# STM32_MPU_IOs.net
KiCad netlist of a schematic drawn in Altium Designer
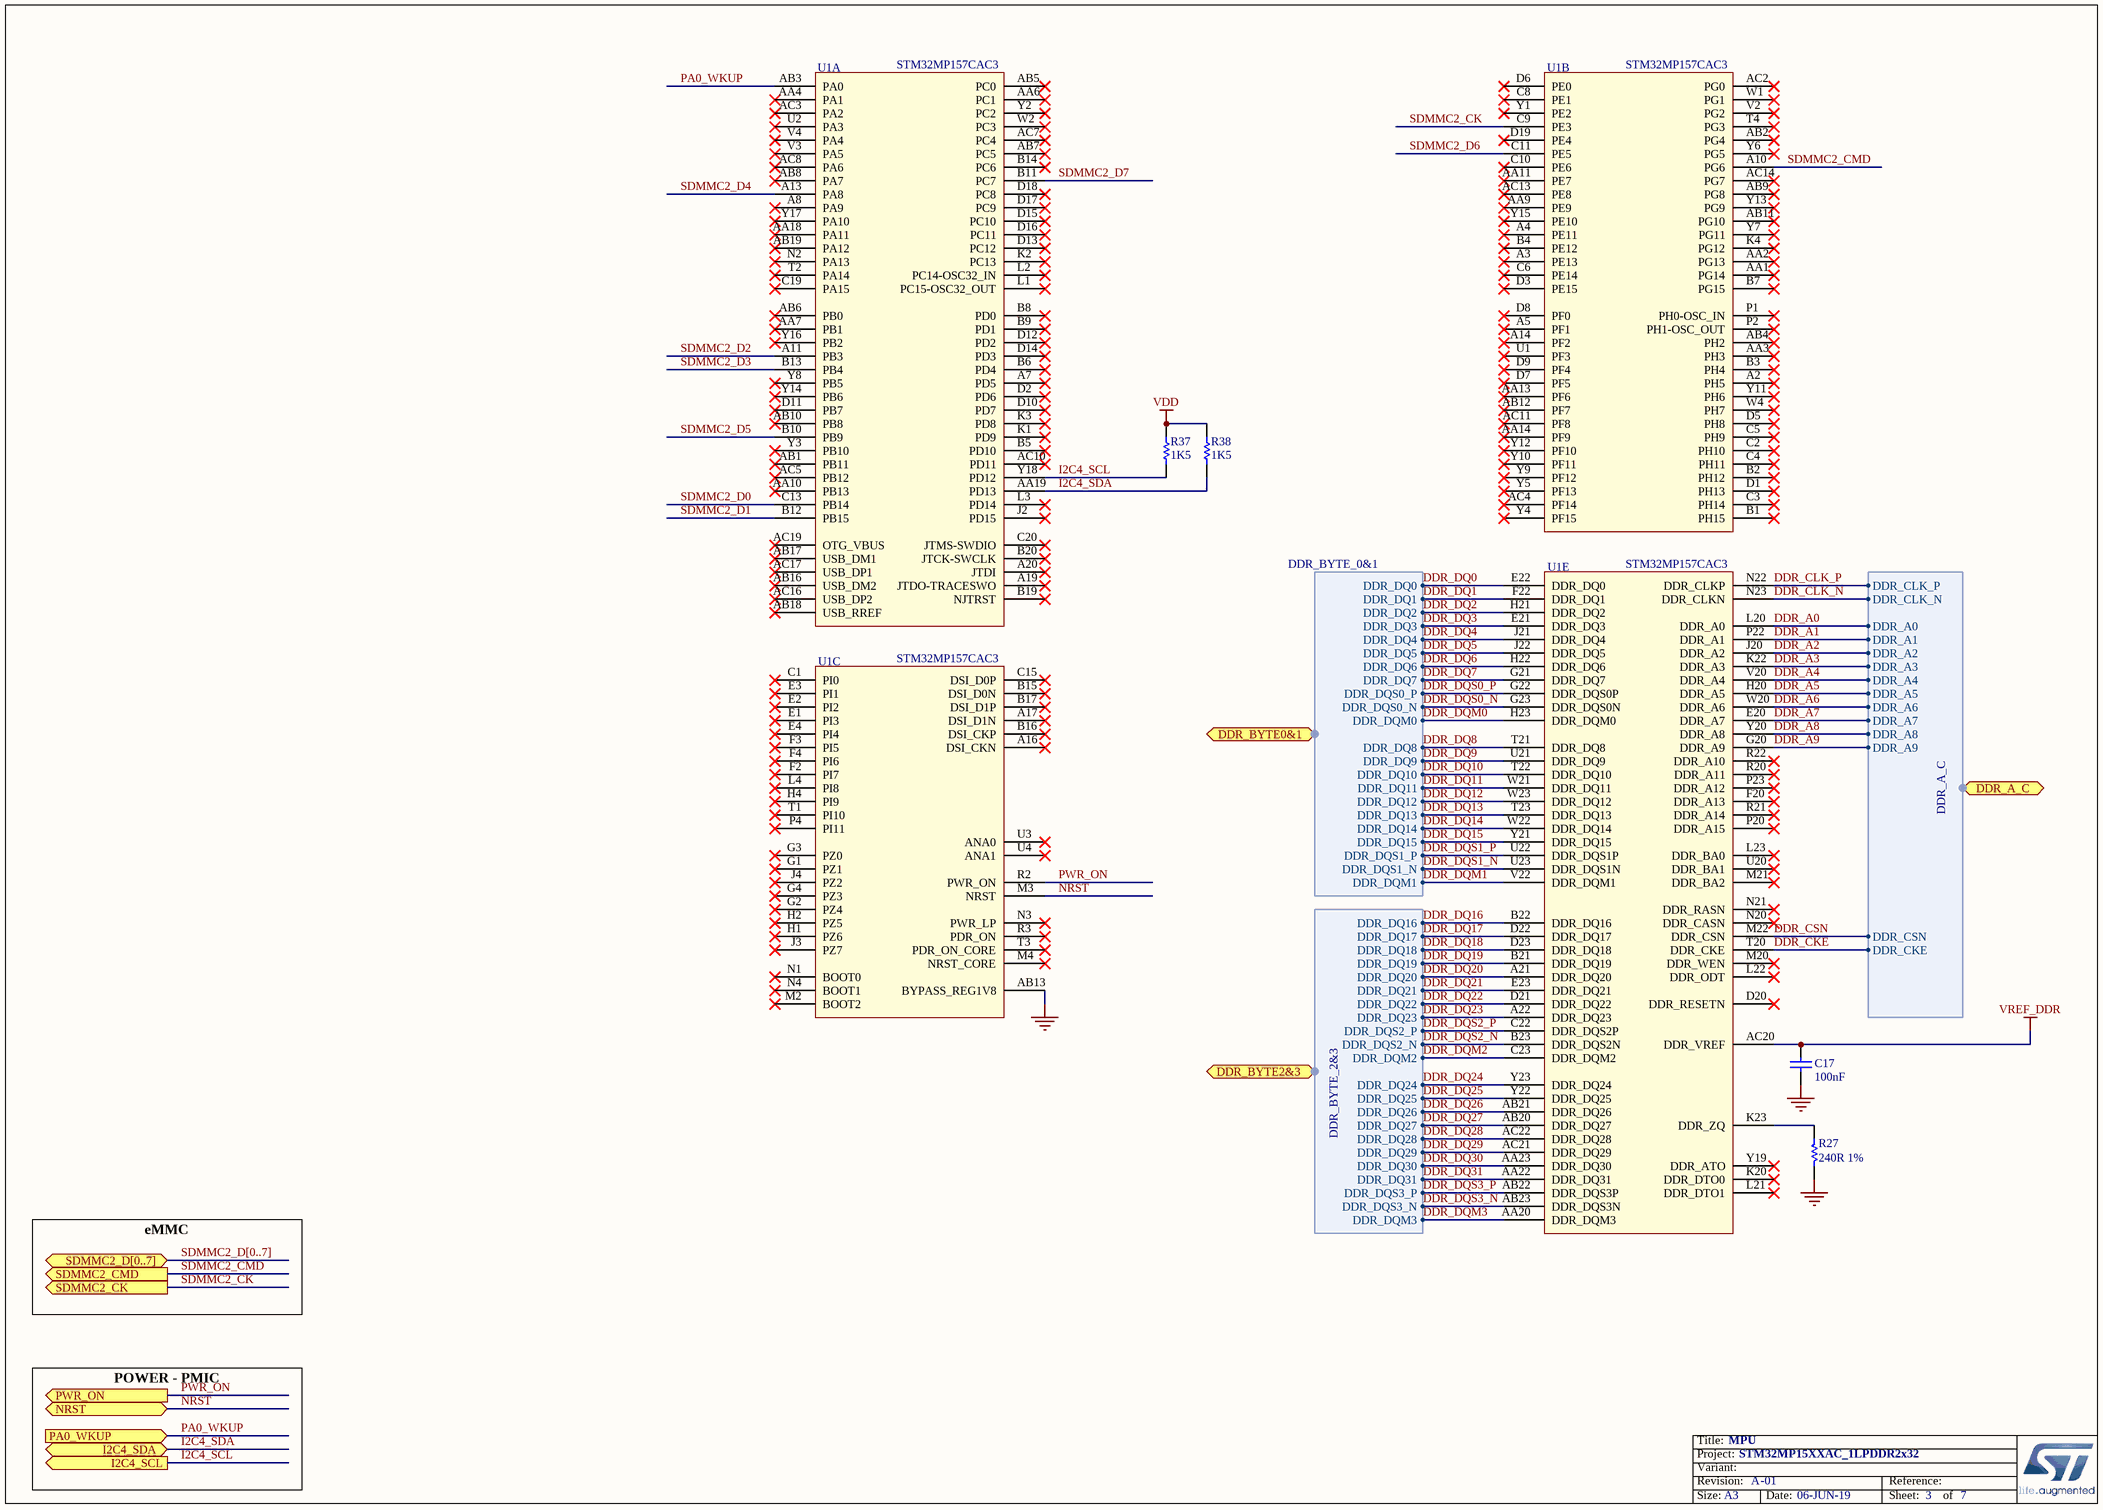
[diagram p0: STM32_MPU_IOs.SchDoc]

(export (version "E")
  (design (tool "Eeschema 10.0.6"))
  (components
    (comp (ref "C17")
      (value "100nF")
      (footprint "C0402")
      (description "Capacitor, MLCC, 100nF, 16V, X7R, 10%, 0402, T=0.5mm")
      (fields
        (field (name "INTERNAL_PART_NUMBER") "MCD-00006")
        (field (name "MANUFACTURER_PART_NUMBER") "CC0402KRX7R7BB104")
        (field (name "PROVIDED_BY") "SUBCO")
      )
      (libsource (lib "MCD_PARTS_database") (part "Capacitor"))
    )
    (comp (ref "R27")
      (value "240R 1%")
      (footprint "R0402")
      (description "Resistor,240R,0402,1%,1/16W")
      (fields
        (field (name "INTERNAL_PART_NUMBER") "MCD-00120")
        (field (name "MANUFACTURER_PART_NUMBER") "RC0402FR-07240RL")
        (field (name "PROVIDED_BY") "SUBCO")
      )
      (libsource (lib "MCD_PARTS_database") (part "Resistor"))
    )
    (comp (ref "R37")
      (value "1K5")
      (footprint "R0402")
      (description "Resistor,1K5,0402,1%,1/16W")
      (fields
        (field (name "INTERNAL_PART_NUMBER") "MCD-00068")
        (field (name "MANUFACTURER_PART_NUMBER") "RC0402FR-071K5L")
        (field (name "PROVIDED_BY") "SUBCO")
      )
      (libsource (lib "MCD_PARTS_database") (part "Resistor"))
    )
    (comp (ref "R38")
      (value "1K5")
      (footprint "R0402")
      (description "Resistor,1K5,0402,1%,1/16W")
      (fields
        (field (name "INTERNAL_PART_NUMBER") "MCD-00068")
        (field (name "MANUFACTURER_PART_NUMBER") "RC0402FR-071K5L")
        (field (name "PROVIDED_BY") "SUBCO")
      )
      (libsource (lib "MCD_PARTS_database") (part "Resistor"))
    )
    (comp (ref "U1")
      (value "STM32MP157CAC3")
      (footprint "ICC_TFBGA361_12X12_STM32MP157CAC3_P050-065")
      (description "MPU TFBGA12x12 secure boot+crypto")
      (fields
        (field (name "INTERNAL_PART_NUMBER") "MCD-00677")
        (field (name "MANUFACTURER") "STMICROELECTRONICS")
        (field (name "PROVIDED_BY") "SUBCO with ST control")
      )
      (libsource (lib "MCD_PARTS_database") (part "STM32MP157CAC3"))
    )
  )
  (nets
    (net (code "4") (name "/DDR_A0") (class "Default")
      (node (ref "U1") (pin "L20") (pinfunction "DDR_A0_L20") (pintype "passive"))
    )
    (net (code "5") (name "/DDR_A1") (class "Default")
      (node (ref "U1") (pin "P22") (pinfunction "DDR_A1_P22") (pintype "passive"))
    )
    (net (code "6") (name "/DDR_A2") (class "Default")
      (node (ref "U1") (pin "J20") (pinfunction "DDR_A2_J20") (pintype "passive"))
    )
    (net (code "7") (name "/DDR_A3") (class "Default")
      (node (ref "U1") (pin "K22") (pinfunction "DDR_A3_K22") (pintype "passive"))
    )
    (net (code "8") (name "/DDR_A4") (class "Default")
      (node (ref "U1") (pin "V20") (pinfunction "DDR_A4_V20") (pintype "passive"))
    )
    (net (code "9") (name "/DDR_A5") (class "Default")
      (node (ref "U1") (pin "H20") (pinfunction "DDR_A5_H20") (pintype "passive"))
    )
    (net (code "10") (name "/DDR_A6") (class "Default")
      (node (ref "U1") (pin "W20") (pinfunction "DDR_A6_W20") (pintype "passive"))
    )
    (net (code "11") (name "/DDR_A7") (class "Default")
      (node (ref "U1") (pin "E20") (pinfunction "DDR_A7_E20") (pintype "passive"))
    )
    (net (code "12") (name "/DDR_A8") (class "Default")
      (node (ref "U1") (pin "Y20") (pinfunction "DDR_A8_Y20") (pintype "passive"))
    )
    (net (code "13") (name "/DDR_A9") (class "Default")
      (node (ref "U1") (pin "G20") (pinfunction "DDR_A9_G20") (pintype "passive"))
    )
    (net (code "14") (name "/DDR_CKE") (class "Default")
      (node (ref "U1") (pin "T20") (pinfunction "DDR_CKE_T20") (pintype "passive"))
    )
    (net (code "15") (name "/DDR_CLK_N") (class "Default")
      (node (ref "U1") (pin "N23") (pinfunction "DDR_CLKN_N23") (pintype "passive"))
    )
    (net (code "16") (name "/DDR_CLK_P") (class "Default")
      (node (ref "U1") (pin "N22") (pinfunction "DDR_CLKP_N22") (pintype "passive"))
    )
    (net (code "17") (name "/DDR_CSN") (class "Default")
      (node (ref "U1") (pin "M22") (pinfunction "DDR_CSN_M22") (pintype "passive"))
    )
    (net (code "18") (name "/DDR_DQ0") (class "Default")
      (node (ref "U1") (pin "E22") (pinfunction "DDR_DQ0_E22") (pintype "passive"))
    )
    (net (code "19") (name "/DDR_DQ1") (class "Default")
      (node (ref "U1") (pin "F22") (pinfunction "DDR_DQ1_F22") (pintype "passive"))
    )
    (net (code "20") (name "/DDR_DQ2") (class "Default")
      (node (ref "U1") (pin "H21") (pinfunction "DDR_DQ2_H21") (pintype "passive"))
    )
    (net (code "21") (name "/DDR_DQ3") (class "Default")
      (node (ref "U1") (pin "E21") (pinfunction "DDR_DQ3_E21") (pintype "passive"))
    )
    (net (code "22") (name "/DDR_DQ4") (class "Default")
      (node (ref "U1") (pin "J21") (pinfunction "DDR_DQ4_J21") (pintype "passive"))
    )
    (net (code "23") (name "/DDR_DQ5") (class "Default")
      (node (ref "U1") (pin "J22") (pinfunction "DDR_DQ5_J22") (pintype "passive"))
    )
    (net (code "24") (name "/DDR_DQ6") (class "Default")
      (node (ref "U1") (pin "H22") (pinfunction "DDR_DQ6_H22") (pintype "passive"))
    )
    (net (code "25") (name "/DDR_DQ7") (class "Default")
      (node (ref "U1") (pin "G21") (pinfunction "DDR_DQ7_G21") (pintype "passive"))
    )
    (net (code "26") (name "/DDR_DQ8") (class "Default")
      (node (ref "U1") (pin "T21") (pinfunction "DDR_DQ8_T21") (pintype "passive"))
    )
    (net (code "27") (name "/DDR_DQ9") (class "Default")
      (node (ref "U1") (pin "U21") (pinfunction "DDR_DQ9_U21") (pintype "passive"))
    )
    (net (code "28") (name "/DDR_DQ10") (class "Default")
      (node (ref "U1") (pin "T22") (pinfunction "DDR_DQ10_T22") (pintype "passive"))
    )
    (net (code "29") (name "/DDR_DQ11") (class "Default")
      (node (ref "U1") (pin "W21") (pinfunction "DDR_DQ11_W21") (pintype "passive"))
    )
    (net (code "30") (name "/DDR_DQ12") (class "Default")
      (node (ref "U1") (pin "W23") (pinfunction "DDR_DQ12_W23") (pintype "passive"))
    )
    (net (code "31") (name "/DDR_DQ13") (class "Default")
      (node (ref "U1") (pin "T23") (pinfunction "DDR_DQ13_T23") (pintype "passive"))
    )
    (net (code "32") (name "/DDR_DQ14") (class "Default")
      (node (ref "U1") (pin "W22") (pinfunction "DDR_DQ14_W22") (pintype "passive"))
    )
    (net (code "33") (name "/DDR_DQ15") (class "Default")
      (node (ref "U1") (pin "Y21") (pinfunction "DDR_DQ15_Y21") (pintype "passive"))
    )
    (net (code "34") (name "/DDR_DQ16") (class "Default")
      (node (ref "U1") (pin "B22") (pinfunction "DDR_DQ16_B22") (pintype "passive"))
    )
    (net (code "35") (name "/DDR_DQ17") (class "Default")
      (node (ref "U1") (pin "D22") (pinfunction "DDR_DQ17_D22") (pintype "passive"))
    )
    (net (code "36") (name "/DDR_DQ18") (class "Default")
      (node (ref "U1") (pin "D23") (pinfunction "DDR_DQ18_D23") (pintype "passive"))
    )
    (net (code "37") (name "/DDR_DQ19") (class "Default")
      (node (ref "U1") (pin "B21") (pinfunction "DDR_DQ19_B21") (pintype "passive"))
    )
    (net (code "38") (name "/DDR_DQ20") (class "Default")
      (node (ref "U1") (pin "A21") (pinfunction "DDR_DQ20_A21") (pintype "passive"))
    )
    (net (code "39") (name "/DDR_DQ21") (class "Default")
      (node (ref "U1") (pin "E23") (pinfunction "DDR_DQ21_E23") (pintype "passive"))
    )
    (net (code "40") (name "/DDR_DQ22") (class "Default")
      (node (ref "U1") (pin "D21") (pinfunction "DDR_DQ22_D21") (pintype "passive"))
    )
    (net (code "41") (name "/DDR_DQ23") (class "Default")
      (node (ref "U1") (pin "A22") (pinfunction "DDR_DQ23_A22") (pintype "passive"))
    )
    (net (code "42") (name "/DDR_DQ24") (class "Default")
      (node (ref "U1") (pin "Y23") (pinfunction "DDR_DQ24_Y23") (pintype "passive"))
    )
    (net (code "43") (name "/DDR_DQ25") (class "Default")
      (node (ref "U1") (pin "Y22") (pinfunction "DDR_DQ25_Y22") (pintype "passive"))
    )
    (net (code "44") (name "/DDR_DQ26") (class "Default")
      (node (ref "U1") (pin "AB21") (pinfunction "DDR_DQ26_AB21") (pintype "passive"))
    )
    (net (code "45") (name "/DDR_DQ27") (class "Default")
      (node (ref "U1") (pin "AB20") (pinfunction "DDR_DQ27_AB20") (pintype "passive"))
    )
    (net (code "46") (name "/DDR_DQ28") (class "Default")
      (node (ref "U1") (pin "AC22") (pinfunction "DDR_DQ28_AC22") (pintype "passive"))
    )
    (net (code "47") (name "/DDR_DQ29") (class "Default")
      (node (ref "U1") (pin "AC21") (pinfunction "DDR_DQ29_AC21") (pintype "passive"))
    )
    (net (code "48") (name "/DDR_DQ30") (class "Default")
      (node (ref "U1") (pin "AA23") (pinfunction "DDR_DQ30_AA23") (pintype "passive"))
    )
    (net (code "49") (name "/DDR_DQ31") (class "Default")
      (node (ref "U1") (pin "AA22") (pinfunction "DDR_DQ31_AA22") (pintype "passive"))
    )
    (net (code "50") (name "/DDR_DQM0") (class "Default")
      (node (ref "U1") (pin "H23") (pinfunction "DDR_DQM0_H23") (pintype "passive"))
    )
    (net (code "51") (name "/DDR_DQM1") (class "Default")
      (node (ref "U1") (pin "V22") (pinfunction "DDR_DQM1_V22") (pintype "passive"))
    )
    (net (code "52") (name "/DDR_DQM2") (class "Default")
      (node (ref "U1") (pin "C23") (pinfunction "DDR_DQM2_C23") (pintype "passive"))
    )
    (net (code "53") (name "/DDR_DQM3") (class "Default")
      (node (ref "U1") (pin "AA20") (pinfunction "DDR_DQM3_AA20") (pintype "passive"))
    )
    (net (code "54") (name "/DDR_DQS0_N") (class "Default")
      (node (ref "U1") (pin "G23") (pinfunction "DDR_DQS0N_G23") (pintype "passive"))
    )
    (net (code "55") (name "/DDR_DQS0_P") (class "Default")
      (node (ref "U1") (pin "G22") (pinfunction "DDR_DQS0P_G22") (pintype "passive"))
    )
    (net (code "56") (name "/DDR_DQS1_N") (class "Default")
      (node (ref "U1") (pin "U23") (pinfunction "DDR_DQS1N_U23") (pintype "passive"))
    )
    (net (code "57") (name "/DDR_DQS1_P") (class "Default")
      (node (ref "U1") (pin "U22") (pinfunction "DDR_DQS1P_U22") (pintype "passive"))
    )
    (net (code "58") (name "/DDR_DQS2_N") (class "Default")
      (node (ref "U1") (pin "B23") (pinfunction "DDR_DQS2N_B23") (pintype "passive"))
    )
    (net (code "59") (name "/DDR_DQS2_P") (class "Default")
      (node (ref "U1") (pin "C22") (pinfunction "DDR_DQS2P_C22") (pintype "passive"))
    )
    (net (code "60") (name "/DDR_DQS3_N") (class "Default")
      (node (ref "U1") (pin "AB23") (pinfunction "DDR_DQS3N_AB23") (pintype "passive"))
    )
    (net (code "61") (name "/DDR_DQS3_P") (class "Default")
      (node (ref "U1") (pin "AB22") (pinfunction "DDR_DQS3P_AB22") (pintype "passive"))
    )
    (net (code "62") (name "/I2C4_SCL") (class "Default")
      (node (ref "R37") (pin "2") (pinfunction "2_2") (pintype "passive"))
      (node (ref "U1") (pin "Y18") (pinfunction "PD12_Y18") (pintype "passive"))
    )
    (net (code "63") (name "/I2C4_SDA") (class "Default")
      (node (ref "R38") (pin "2") (pinfunction "2_2") (pintype "passive"))
      (node (ref "U1") (pin "AA19") (pinfunction "PD13_AA19") (pintype "passive"))
    )
    (net (code "64") (name "/NRST") (class "Default")
      (node (ref "U1") (pin "M3") (pinfunction "NRST_M3") (pintype "passive"))
    )
    (net (code "65") (name "/PA0_WKUP") (class "Default")
      (node (ref "U1") (pin "AB3") (pinfunction "PA0_AB3") (pintype "passive"))
    )
    (net (code "66") (name "/PWR_ON") (class "Default")
      (node (ref "U1") (pin "R2") (pinfunction "PWR_ON_R2") (pintype "passive"))
    )
    (net (code "67") (name "/SDMMC2_CK") (class "Default")
      (node (ref "U1") (pin "C9") (pinfunction "PE3_C9") (pintype "passive"))
    )
    (net (code "68") (name "/SDMMC2_CMD") (class "Default")
      (node (ref "U1") (pin "A10") (pinfunction "PG6_A10") (pintype "passive"))
    )
    (net (code "69") (name "/SDMMC2_D0") (class "Default")
      (node (ref "U1") (pin "C13") (pinfunction "PB14_C13") (pintype "passive"))
    )
    (net (code "70") (name "/SDMMC2_D1") (class "Default")
      (node (ref "U1") (pin "B12") (pinfunction "PB15_B12") (pintype "passive"))
    )
    (net (code "71") (name "/SDMMC2_D2") (class "Default")
      (node (ref "U1") (pin "A11") (pinfunction "PB3_A11") (pintype "passive"))
    )
    (net (code "72") (name "/SDMMC2_D3") (class "Default")
      (node (ref "U1") (pin "B13") (pinfunction "PB4_B13") (pintype "passive"))
    )
    (net (code "73") (name "/SDMMC2_D4") (class "Default")
      (node (ref "U1") (pin "A13") (pinfunction "PA8_A13") (pintype "passive"))
    )
    (net (code "74") (name "/SDMMC2_D5") (class "Default")
      (node (ref "U1") (pin "B10") (pinfunction "PB9_B10") (pintype "passive"))
    )
    (net (code "75") (name "/SDMMC2_D6") (class "Default")
      (node (ref "U1") (pin "C11") (pinfunction "PE5_C11") (pintype "passive"))
    )
    (net (code "76") (name "/SDMMC2_D7") (class "Default")
      (node (ref "U1") (pin "B11") (pinfunction "PC7_B11") (pintype "passive"))
    )
    (net (code "81") (name "GND") (class "Default")
      (node (ref "C17") (pin "2") (pinfunction "2_2") (pintype "passive"))
      (node (ref "R27") (pin "2") (pinfunction "2_2") (pintype "passive"))
      (node (ref "U1") (pin "AB13") (pinfunction "BYPASS_REG1V8_AB13") (pintype "passive"))
    )
    (net (code "82") (name "Net-(U1E-DDR_ZQ)") (class "Default")
      (node (ref "R27") (pin "1") (pinfunction "1_1") (pintype "passive"))
      (node (ref "U1") (pin "K23") (pinfunction "DDR_ZQ_K23") (pintype "passive"))
    )
    (net (code "83") (name "VDD") (class "Default")
      (node (ref "R37") (pin "1") (pinfunction "1_1") (pintype "passive"))
      (node (ref "R38") (pin "1") (pinfunction "1_1") (pintype "passive"))
    )
    (net (code "84") (name "VREF_DDR") (class "Default")
      (node (ref "C17") (pin "1") (pinfunction "1_1") (pintype "passive"))
      (node (ref "U1") (pin "AC20") (pinfunction "DDR_VREF_AC20") (pintype "passive"))
    )
    (net (code "85") (name "unconnected-(U1A-JTCK-SWCLK-PadB20)") (class "Default")
      (node (ref "U1") (pin "B20") (pinfunction "JTCK-SWCLK_B20") (pintype "passive+no_connect"))
    )
    (net (code "86") (name "unconnected-(U1A-JTDI-PadA20)") (class "Default")
      (node (ref "U1") (pin "A20") (pinfunction "JTDI_A20") (pintype "passive+no_connect"))
    )
    (net (code "87") (name "unconnected-(U1A-JTDO-TRACESWO-PadA19)") (class "Default")
      (node (ref "U1") (pin "A19") (pinfunction "JTDO-TRACESWO_A19") (pintype "passive+no_connect"))
    )
    (net (code "88") (name "unconnected-(U1A-JTMS-SWDIO-PadC20)") (class "Default")
      (node (ref "U1") (pin "C20") (pinfunction "JTMS-SWDIO_C20") (pintype "passive+no_connect"))
    )
    (net (code "89") (name "unconnected-(U1A-NJTRST-PadB19)") (class "Default")
      (node (ref "U1") (pin "B19") (pinfunction "NJTRST_B19") (pintype "passive+no_connect"))
    )
    (net (code "90") (name "unconnected-(U1A-OTG_VBUS-PadAC19)") (class "Default")
      (node (ref "U1") (pin "AC19") (pinfunction "OTG_VBUS_AC19") (pintype "passive+no_connect"))
    )
    (net (code "91") (name "unconnected-(U1A-PA1-PadAA4)") (class "Default")
      (node (ref "U1") (pin "AA4") (pinfunction "PA1_AA4") (pintype "passive+no_connect"))
    )
    (net (code "92") (name "unconnected-(U1A-PA2-PadAC3)") (class "Default")
      (node (ref "U1") (pin "AC3") (pinfunction "PA2_AC3") (pintype "passive+no_connect"))
    )
    (net (code "93") (name "unconnected-(U1A-PA3-PadU2)") (class "Default")
      (node (ref "U1") (pin "U2") (pinfunction "PA3_U2") (pintype "passive+no_connect"))
    )
    (net (code "94") (name "unconnected-(U1A-PA4-PadV4)") (class "Default")
      (node (ref "U1") (pin "V4") (pinfunction "PA4_V4") (pintype "passive+no_connect"))
    )
    (net (code "95") (name "unconnected-(U1A-PA5-PadV3)") (class "Default")
      (node (ref "U1") (pin "V3") (pinfunction "PA5_V3") (pintype "passive+no_connect"))
    )
    (net (code "96") (name "unconnected-(U1A-PA6-PadAC8)") (class "Default")
      (node (ref "U1") (pin "AC8") (pinfunction "PA6_AC8") (pintype "passive+no_connect"))
    )
    (net (code "97") (name "unconnected-(U1A-PA7-PadAB8)") (class "Default")
      (node (ref "U1") (pin "AB8") (pinfunction "PA7_AB8") (pintype "passive+no_connect"))
    )
    (net (code "98") (name "unconnected-(U1A-PA9-PadA8)") (class "Default")
      (node (ref "U1") (pin "A8") (pinfunction "PA9_A8") (pintype "passive+no_connect"))
    )
    (net (code "99") (name "unconnected-(U1A-PA10-PadY17)") (class "Default")
      (node (ref "U1") (pin "Y17") (pinfunction "PA10_Y17") (pintype "passive+no_connect"))
    )
    (net (code "100") (name "unconnected-(U1A-PA11-PadAA18)") (class "Default")
      (node (ref "U1") (pin "AA18") (pinfunction "PA11_AA18") (pintype "passive+no_connect"))
    )
    (net (code "101") (name "unconnected-(U1A-PA12-PadAB19)") (class "Default")
      (node (ref "U1") (pin "AB19") (pinfunction "PA12_AB19") (pintype "passive+no_connect"))
    )
    (net (code "102") (name "unconnected-(U1A-PA13-PadN2)") (class "Default")
      (node (ref "U1") (pin "N2") (pinfunction "PA13_N2") (pintype "passive+no_connect"))
    )
    (net (code "103") (name "unconnected-(U1A-PA14-PadT2)") (class "Default")
      (node (ref "U1") (pin "T2") (pinfunction "PA14_T2") (pintype "passive+no_connect"))
    )
    (net (code "104") (name "unconnected-(U1A-PA15-PadC19)") (class "Default")
      (node (ref "U1") (pin "C19") (pinfunction "PA15_C19") (pintype "passive+no_connect"))
    )
    (net (code "105") (name "unconnected-(U1A-PB0-PadAB6)") (class "Default")
      (node (ref "U1") (pin "AB6") (pinfunction "PB0_AB6") (pintype "passive+no_connect"))
    )
    (net (code "106") (name "unconnected-(U1A-PB1-PadAA7)") (class "Default")
      (node (ref "U1") (pin "AA7") (pinfunction "PB1_AA7") (pintype "passive+no_connect"))
    )
    (net (code "107") (name "unconnected-(U1A-PB2-PadY16)") (class "Default")
      (node (ref "U1") (pin "Y16") (pinfunction "PB2_Y16") (pintype "passive+no_connect"))
    )
    (net (code "108") (name "unconnected-(U1A-PB5-PadY8)") (class "Default")
      (node (ref "U1") (pin "Y8") (pinfunction "PB5_Y8") (pintype "passive+no_connect"))
    )
    (net (code "109") (name "unconnected-(U1A-PB6-PadY14)") (class "Default")
      (node (ref "U1") (pin "Y14") (pinfunction "PB6_Y14") (pintype "passive+no_connect"))
    )
    (net (code "110") (name "unconnected-(U1A-PB7-PadD11)") (class "Default")
      (node (ref "U1") (pin "D11") (pinfunction "PB7_D11") (pintype "passive+no_connect"))
    )
    (net (code "111") (name "unconnected-(U1A-PB8-PadAB10)") (class "Default")
      (node (ref "U1") (pin "AB10") (pinfunction "PB8_AB10") (pintype "passive+no_connect"))
    )
    (net (code "112") (name "unconnected-(U1A-PB10-PadY3)") (class "Default")
      (node (ref "U1") (pin "Y3") (pinfunction "PB10_Y3") (pintype "passive+no_connect"))
    )
    (net (code "113") (name "unconnected-(U1A-PB11-PadAB1)") (class "Default")
      (node (ref "U1") (pin "AB1") (pinfunction "PB11_AB1") (pintype "passive+no_connect"))
    )
    (net (code "114") (name "unconnected-(U1A-PB12-PadAC5)") (class "Default")
      (node (ref "U1") (pin "AC5") (pinfunction "PB12_AC5") (pintype "passive+no_connect"))
    )
    (net (code "115") (name "unconnected-(U1A-PB13-PadAA10)") (class "Default")
      (node (ref "U1") (pin "AA10") (pinfunction "PB13_AA10") (pintype "passive+no_connect"))
    )
    (net (code "116") (name "unconnected-(U1A-PC0-PadAB5)") (class "Default")
      (node (ref "U1") (pin "AB5") (pinfunction "PC0_AB5") (pintype "passive+no_connect"))
    )
    (net (code "117") (name "unconnected-(U1A-PC1-PadAA6)") (class "Default")
      (node (ref "U1") (pin "AA6") (pinfunction "PC1_AA6") (pintype "passive+no_connect"))
    )
    (net (code "118") (name "unconnected-(U1A-PC2-PadY2)") (class "Default")
      (node (ref "U1") (pin "Y2") (pinfunction "PC2_Y2") (pintype "passive+no_connect"))
    )
    (net (code "119") (name "unconnected-(U1A-PC3-PadW2)") (class "Default")
      (node (ref "U1") (pin "W2") (pinfunction "PC3_W2") (pintype "passive+no_connect"))
    )
    (net (code "120") (name "unconnected-(U1A-PC4-PadAC7)") (class "Default")
      (node (ref "U1") (pin "AC7") (pinfunction "PC4_AC7") (pintype "passive+no_connect"))
    )
    (net (code "121") (name "unconnected-(U1A-PC5-PadAB7)") (class "Default")
      (node (ref "U1") (pin "AB7") (pinfunction "PC5_AB7") (pintype "passive+no_connect"))
    )
    (net (code "122") (name "unconnected-(U1A-PC6-PadB14)") (class "Default")
      (node (ref "U1") (pin "B14") (pinfunction "PC6_B14") (pintype "passive+no_connect"))
    )
    (net (code "123") (name "unconnected-(U1A-PC8-PadD18)") (class "Default")
      (node (ref "U1") (pin "D18") (pinfunction "PC8_D18") (pintype "passive+no_connect"))
    )
    (net (code "124") (name "unconnected-(U1A-PC9-PadD17)") (class "Default")
      (node (ref "U1") (pin "D17") (pinfunction "PC9_D17") (pintype "passive+no_connect"))
    )
    (net (code "125") (name "unconnected-(U1A-PC10-PadD15)") (class "Default")
      (node (ref "U1") (pin "D15") (pinfunction "PC10_D15") (pintype "passive+no_connect"))
    )
    (net (code "126") (name "unconnected-(U1A-PC11-PadD16)") (class "Default")
      (node (ref "U1") (pin "D16") (pinfunction "PC11_D16") (pintype "passive+no_connect"))
    )
    (net (code "127") (name "unconnected-(U1A-PC12-PadD13)") (class "Default")
      (node (ref "U1") (pin "D13") (pinfunction "PC12_D13") (pintype "passive+no_connect"))
    )
    (net (code "128") (name "unconnected-(U1A-PC13-PadK2)") (class "Default")
      (node (ref "U1") (pin "K2") (pinfunction "PC13_K2") (pintype "passive+no_connect"))
    )
    (net (code "129") (name "unconnected-(U1A-PC14-OSC32_IN-PadL2)") (class "Default")
      (node (ref "U1") (pin "L2") (pinfunction "PC14-OSC32_IN_L2") (pintype "passive+no_connect"))
    )
    (net (code "130") (name "unconnected-(U1A-PC15-OSC32_OUT-PadL1)") (class "Default")
      (node (ref "U1") (pin "L1") (pinfunction "PC15-OSC32_OUT_L1") (pintype "passive+no_connect"))
    )
    (net (code "131") (name "unconnected-(U1A-PD0-PadB8)") (class "Default")
      (node (ref "U1") (pin "B8") (pinfunction "PD0_B8") (pintype "passive+no_connect"))
    )
    (net (code "132") (name "unconnected-(U1A-PD1-PadB9)") (class "Default")
      (node (ref "U1") (pin "B9") (pinfunction "PD1_B9") (pintype "passive+no_connect"))
    )
    (net (code "133") (name "unconnected-(U1A-PD2-PadD12)") (class "Default")
      (node (ref "U1") (pin "D12") (pinfunction "PD2_D12") (pintype "passive+no_connect"))
    )
    (net (code "134") (name "unconnected-(U1A-PD3-PadD14)") (class "Default")
      (node (ref "U1") (pin "D14") (pinfunction "PD3_D14") (pintype "passive+no_connect"))
    )
    (net (code "135") (name "unconnected-(U1A-PD4-PadB6)") (class "Default")
      (node (ref "U1") (pin "B6") (pinfunction "PD4_B6") (pintype "passive+no_connect"))
    )
    (net (code "136") (name "unconnected-(U1A-PD5-PadA7)") (class "Default")
      (node (ref "U1") (pin "A7") (pinfunction "PD5_A7") (pintype "passive+no_connect"))
    )
    (net (code "137") (name "unconnected-(U1A-PD6-PadD2)") (class "Default")
      (node (ref "U1") (pin "D2") (pinfunction "PD6_D2") (pintype "passive+no_connect"))
    )
    (net (code "138") (name "unconnected-(U1A-PD7-PadD10)") (class "Default")
      (node (ref "U1") (pin "D10") (pinfunction "PD7_D10") (pintype "passive+no_connect"))
    )
    (net (code "139") (name "unconnected-(U1A-PD8-PadK3)") (class "Default")
      (node (ref "U1") (pin "K3") (pinfunction "PD8_K3") (pintype "passive+no_connect"))
    )
    (net (code "140") (name "unconnected-(U1A-PD9-PadK1)") (class "Default")
      (node (ref "U1") (pin "K1") (pinfunction "PD9_K1") (pintype "passive+no_connect"))
    )
    (net (code "141") (name "unconnected-(U1A-PD10-PadB5)") (class "Default")
      (node (ref "U1") (pin "B5") (pinfunction "PD10_B5") (pintype "passive+no_connect"))
    )
    (net (code "142") (name "unconnected-(U1A-PD11-PadAC10)") (class "Default")
      (node (ref "U1") (pin "AC10") (pinfunction "PD11_AC10") (pintype "passive+no_connect"))
    )
    (net (code "143") (name "unconnected-(U1A-PD14-PadL3)") (class "Default")
      (node (ref "U1") (pin "L3") (pinfunction "PD14_L3") (pintype "passive+no_connect"))
    )
    (net (code "144") (name "unconnected-(U1A-PD15-PadJ2)") (class "Default")
      (node (ref "U1") (pin "J2") (pinfunction "PD15_J2") (pintype "passive+no_connect"))
    )
    (net (code "145") (name "unconnected-(U1A-USB_DM1-PadAB17)") (class "Default")
      (node (ref "U1") (pin "AB17") (pinfunction "USB_DM1_AB17") (pintype "passive+no_connect"))
    )
    (net (code "146") (name "unconnected-(U1A-USB_DM2-PadAB16)") (class "Default")
      (node (ref "U1") (pin "AB16") (pinfunction "USB_DM2_AB16") (pintype "passive+no_connect"))
    )
    (net (code "147") (name "unconnected-(U1A-USB_DP1-PadAC17)") (class "Default")
      (node (ref "U1") (pin "AC17") (pinfunction "USB_DP1_AC17") (pintype "passive+no_connect"))
    )
    (net (code "148") (name "unconnected-(U1A-USB_DP2-PadAC16)") (class "Default")
      (node (ref "U1") (pin "AC16") (pinfunction "USB_DP2_AC16") (pintype "passive+no_connect"))
    )
    (net (code "149") (name "unconnected-(U1A-USB_RREF-PadAB18)") (class "Default")
      (node (ref "U1") (pin "AB18") (pinfunction "USB_RREF_AB18") (pintype "passive+no_connect"))
    )
    (net (code "150") (name "unconnected-(U1B-PE0-PadD6)") (class "Default")
      (node (ref "U1") (pin "D6") (pinfunction "PE0_D6") (pintype "passive+no_connect"))
    )
    (net (code "151") (name "unconnected-(U1B-PE1-PadC8)") (class "Default")
      (node (ref "U1") (pin "C8") (pinfunction "PE1_C8") (pintype "passive+no_connect"))
    )
    (net (code "152") (name "unconnected-(U1B-PE2-PadY1)") (class "Default")
      (node (ref "U1") (pin "Y1") (pinfunction "PE2_Y1") (pintype "passive+no_connect"))
    )
    (net (code "153") (name "unconnected-(U1B-PE4-PadD19)") (class "Default")
      (node (ref "U1") (pin "D19") (pinfunction "PE4_D19") (pintype "passive+no_connect"))
    )
    (net (code "154") (name "unconnected-(U1B-PE6-PadC10)") (class "Default")
      (node (ref "U1") (pin "C10") (pinfunction "PE6_C10") (pintype "passive+no_connect"))
    )
    (net (code "155") (name "unconnected-(U1B-PE7-PadAA11)") (class "Default")
      (node (ref "U1") (pin "AA11") (pinfunction "PE7_AA11") (pintype "passive+no_connect"))
    )
    (net (code "156") (name "unconnected-(U1B-PE8-PadAC13)") (class "Default")
      (node (ref "U1") (pin "AC13") (pinfunction "PE8_AC13") (pintype "passive+no_connect"))
    )
    (net (code "157") (name "unconnected-(U1B-PE9-PadAA9)") (class "Default")
      (node (ref "U1") (pin "AA9") (pinfunction "PE9_AA9") (pintype "passive+no_connect"))
    )
    (net (code "158") (name "unconnected-(U1B-PE10-PadY15)") (class "Default")
      (node (ref "U1") (pin "Y15") (pinfunction "PE10_Y15") (pintype "passive+no_connect"))
    )
    (net (code "159") (name "unconnected-(U1B-PE11-PadA4)") (class "Default")
      (node (ref "U1") (pin "A4") (pinfunction "PE11_A4") (pintype "passive+no_connect"))
    )
    (net (code "160") (name "unconnected-(U1B-PE12-PadB4)") (class "Default")
      (node (ref "U1") (pin "B4") (pinfunction "PE12_B4") (pintype "passive+no_connect"))
    )
    (net (code "161") (name "unconnected-(U1B-PE13-PadA3)") (class "Default")
      (node (ref "U1") (pin "A3") (pinfunction "PE13_A3") (pintype "passive+no_connect"))
    )
    (net (code "162") (name "unconnected-(U1B-PE14-PadC6)") (class "Default")
      (node (ref "U1") (pin "C6") (pinfunction "PE14_C6") (pintype "passive+no_connect"))
    )
    (net (code "163") (name "unconnected-(U1B-PE15-PadD3)") (class "Default")
      (node (ref "U1") (pin "D3") (pinfunction "PE15_D3") (pintype "passive+no_connect"))
    )
    (net (code "164") (name "unconnected-(U1B-PF0-PadD8)") (class "Default")
      (node (ref "U1") (pin "D8") (pinfunction "PF0_D8") (pintype "passive+no_connect"))
    )
    (net (code "165") (name "unconnected-(U1B-PF1-PadA5)") (class "Default")
      (node (ref "U1") (pin "A5") (pinfunction "PF1_A5") (pintype "passive+no_connect"))
    )
    (net (code "166") (name "unconnected-(U1B-PF2-PadA14)") (class "Default")
      (node (ref "U1") (pin "A14") (pinfunction "PF2_A14") (pintype "passive+no_connect"))
    )
    (net (code "167") (name "unconnected-(U1B-PF3-PadU1)") (class "Default")
      (node (ref "U1") (pin "U1") (pinfunction "PF3_U1") (pintype "passive+no_connect"))
    )
    (net (code "168") (name "unconnected-(U1B-PF4-PadD9)") (class "Default")
      (node (ref "U1") (pin "D9") (pinfunction "PF4_D9") (pintype "passive+no_connect"))
    )
    (net (code "169") (name "unconnected-(U1B-PF5-PadD7)") (class "Default")
      (node (ref "U1") (pin "D7") (pinfunction "PF5_D7") (pintype "passive+no_connect"))
    )
    (net (code "170") (name "unconnected-(U1B-PF6-PadAA13)") (class "Default")
      (node (ref "U1") (pin "AA13") (pinfunction "PF6_AA13") (pintype "passive+no_connect"))
    )
    (net (code "171") (name "unconnected-(U1B-PF7-PadAB12)") (class "Default")
      (node (ref "U1") (pin "AB12") (pinfunction "PF7_AB12") (pintype "passive+no_connect"))
    )
    (net (code "172") (name "unconnected-(U1B-PF8-PadAC11)") (class "Default")
      (node (ref "U1") (pin "AC11") (pinfunction "PF8_AC11") (pintype "passive+no_connect"))
    )
    (net (code "173") (name "unconnected-(U1B-PF9-PadAA14)") (class "Default")
      (node (ref "U1") (pin "AA14") (pinfunction "PF9_AA14") (pintype "passive+no_connect"))
    )
    (net (code "174") (name "unconnected-(U1B-PF10-PadY12)") (class "Default")
      (node (ref "U1") (pin "Y12") (pinfunction "PF10_Y12") (pintype "passive+no_connect"))
    )
    (net (code "175") (name "unconnected-(U1B-PF11-PadY10)") (class "Default")
      (node (ref "U1") (pin "Y10") (pinfunction "PF11_Y10") (pintype "passive+no_connect"))
    )
    (net (code "176") (name "unconnected-(U1B-PF12-PadY9)") (class "Default")
      (node (ref "U1") (pin "Y9") (pinfunction "PF12_Y9") (pintype "passive+no_connect"))
    )
    (net (code "177") (name "unconnected-(U1B-PF13-PadY5)") (class "Default")
      (node (ref "U1") (pin "Y5") (pinfunction "PF13_Y5") (pintype "passive+no_connect"))
    )
    (net (code "178") (name "unconnected-(U1B-PF14-PadAC4)") (class "Default")
      (node (ref "U1") (pin "AC4") (pinfunction "PF14_AC4") (pintype "passive+no_connect"))
    )
    (net (code "179") (name "unconnected-(U1B-PF15-PadY4)") (class "Default")
      (node (ref "U1") (pin "Y4") (pinfunction "PF15_Y4") (pintype "passive+no_connect"))
    )
    (net (code "180") (name "unconnected-(U1B-PG0-PadAC2)") (class "Default")
      (node (ref "U1") (pin "AC2") (pinfunction "PG0_AC2") (pintype "passive+no_connect"))
    )
    (net (code "181") (name "unconnected-(U1B-PG1-PadW1)") (class "Default")
      (node (ref "U1") (pin "W1") (pinfunction "PG1_W1") (pintype "passive+no_connect"))
    )
    (net (code "182") (name "unconnected-(U1B-PG2-PadV2)") (class "Default")
      (node (ref "U1") (pin "V2") (pinfunction "PG2_V2") (pintype "passive+no_connect"))
    )
    (net (code "183") (name "unconnected-(U1B-PG3-PadT4)") (class "Default")
      (node (ref "U1") (pin "T4") (pinfunction "PG3_T4") (pintype "passive+no_connect"))
    )
    (net (code "184") (name "unconnected-(U1B-PG4-PadAB2)") (class "Default")
      (node (ref "U1") (pin "AB2") (pinfunction "PG4_AB2") (pintype "passive+no_connect"))
    )
    (net (code "185") (name "unconnected-(U1B-PG5-PadY6)") (class "Default")
      (node (ref "U1") (pin "Y6") (pinfunction "PG5_Y6") (pintype "passive+no_connect"))
    )
    (net (code "186") (name "unconnected-(U1B-PG7-PadAC14)") (class "Default")
      (node (ref "U1") (pin "AC14") (pinfunction "PG7_AC14") (pintype "passive+no_connect"))
    )
    (net (code "187") (name "unconnected-(U1B-PG8-PadAB9)") (class "Default")
      (node (ref "U1") (pin "AB9") (pinfunction "PG8_AB9") (pintype "passive+no_connect"))
    )
    (net (code "188") (name "unconnected-(U1B-PG9-PadY13)") (class "Default")
      (node (ref "U1") (pin "Y13") (pinfunction "PG9_Y13") (pintype "passive+no_connect"))
    )
    (net (code "189") (name "unconnected-(U1B-PG10-PadAB11)") (class "Default")
      (node (ref "U1") (pin "AB11") (pinfunction "PG10_AB11") (pintype "passive+no_connect"))
    )
    (net (code "190") (name "unconnected-(U1B-PG11-PadY7)") (class "Default")
      (node (ref "U1") (pin "Y7") (pinfunction "PG11_Y7") (pintype "passive+no_connect"))
    )
    (net (code "191") (name "unconnected-(U1B-PG12-PadK4)") (class "Default")
      (node (ref "U1") (pin "K4") (pinfunction "PG12_K4") (pintype "passive+no_connect"))
    )
    (net (code "192") (name "unconnected-(U1B-PG13-PadAA2)") (class "Default")
      (node (ref "U1") (pin "AA2") (pinfunction "PG13_AA2") (pintype "passive+no_connect"))
    )
    (net (code "193") (name "unconnected-(U1B-PG14-PadAA1)") (class "Default")
      (node (ref "U1") (pin "AA1") (pinfunction "PG14_AA1") (pintype "passive+no_connect"))
    )
    (net (code "194") (name "unconnected-(U1B-PG15-PadB7)") (class "Default")
      (node (ref "U1") (pin "B7") (pinfunction "PG15_B7") (pintype "passive+no_connect"))
    )
    (net (code "195") (name "unconnected-(U1B-PH0-OSC_IN-PadP1)") (class "Default")
      (node (ref "U1") (pin "P1") (pinfunction "PH0-OSC_IN_P1") (pintype "passive+no_connect"))
    )
    (net (code "196") (name "unconnected-(U1B-PH1-OSC_OUT-PadP2)") (class "Default")
      (node (ref "U1") (pin "P2") (pinfunction "PH1-OSC_OUT_P2") (pintype "passive+no_connect"))
    )
    (net (code "197") (name "unconnected-(U1B-PH2-PadAB4)") (class "Default")
      (node (ref "U1") (pin "AB4") (pinfunction "PH2_AB4") (pintype "passive+no_connect"))
    )
    (net (code "198") (name "unconnected-(U1B-PH3-PadAA3)") (class "Default")
      (node (ref "U1") (pin "AA3") (pinfunction "PH3_AA3") (pintype "passive+no_connect"))
    )
    (net (code "199") (name "unconnected-(U1B-PH4-PadB3)") (class "Default")
      (node (ref "U1") (pin "B3") (pinfunction "PH4_B3") (pintype "passive+no_connect"))
    )
    (net (code "200") (name "unconnected-(U1B-PH5-PadA2)") (class "Default")
      (node (ref "U1") (pin "A2") (pinfunction "PH5_A2") (pintype "passive+no_connect"))
    )
    (net (code "201") (name "unconnected-(U1B-PH6-PadY11)") (class "Default")
      (node (ref "U1") (pin "Y11") (pinfunction "PH6_Y11") (pintype "passive+no_connect"))
    )
    (net (code "202") (name "unconnected-(U1B-PH7-PadW4)") (class "Default")
      (node (ref "U1") (pin "W4") (pinfunction "PH7_W4") (pintype "passive+no_connect"))
    )
    (net (code "203") (name "unconnected-(U1B-PH8-PadD5)") (class "Default")
      (node (ref "U1") (pin "D5") (pinfunction "PH8_D5") (pintype "passive+no_connect"))
    )
    (net (code "204") (name "unconnected-(U1B-PH9-PadC5)") (class "Default")
      (node (ref "U1") (pin "C5") (pinfunction "PH9_C5") (pintype "passive+no_connect"))
    )
    (net (code "205") (name "unconnected-(U1B-PH10-PadC2)") (class "Default")
      (node (ref "U1") (pin "C2") (pinfunction "PH10_C2") (pintype "passive+no_connect"))
    )
    (net (code "206") (name "unconnected-(U1B-PH11-PadC4)") (class "Default")
      (node (ref "U1") (pin "C4") (pinfunction "PH11_C4") (pintype "passive+no_connect"))
    )
    (net (code "207") (name "unconnected-(U1B-PH12-PadB2)") (class "Default")
      (node (ref "U1") (pin "B2") (pinfunction "PH12_B2") (pintype "passive+no_connect"))
    )
    (net (code "208") (name "unconnected-(U1B-PH13-PadD1)") (class "Default")
      (node (ref "U1") (pin "D1") (pinfunction "PH13_D1") (pintype "passive+no_connect"))
    )
    (net (code "209") (name "unconnected-(U1B-PH14-PadC3)") (class "Default")
      (node (ref "U1") (pin "C3") (pinfunction "PH14_C3") (pintype "passive+no_connect"))
    )
    (net (code "210") (name "unconnected-(U1B-PH15-PadB1)") (class "Default")
      (node (ref "U1") (pin "B1") (pinfunction "PH15_B1") (pintype "passive+no_connect"))
    )
    (net (code "211") (name "unconnected-(U1C-ANA0-PadU3)") (class "Default")
      (node (ref "U1") (pin "U3") (pinfunction "ANA0_U3") (pintype "passive+no_connect"))
    )
    (net (code "212") (name "unconnected-(U1C-ANA1-PadU4)") (class "Default")
      (node (ref "U1") (pin "U4") (pinfunction "ANA1_U4") (pintype "passive+no_connect"))
    )
    (net (code "213") (name "unconnected-(U1C-BOOT0-PadN1)") (class "Default")
      (node (ref "U1") (pin "N1") (pinfunction "BOOT0_N1") (pintype "passive+no_connect"))
    )
    (net (code "214") (name "unconnected-(U1C-BOOT1-PadN4)") (class "Default")
      (node (ref "U1") (pin "N4") (pinfunction "BOOT1_N4") (pintype "passive+no_connect"))
    )
    (net (code "215") (name "unconnected-(U1C-BOOT2-PadM2)") (class "Default")
      (node (ref "U1") (pin "M2") (pinfunction "BOOT2_M2") (pintype "passive+no_connect"))
    )
    (net (code "216") (name "unconnected-(U1C-DSI_CKN-PadA16)") (class "Default")
      (node (ref "U1") (pin "A16") (pinfunction "DSI_CKN_A16") (pintype "passive+no_connect"))
    )
    (net (code "217") (name "unconnected-(U1C-DSI_CKP-PadB16)") (class "Default")
      (node (ref "U1") (pin "B16") (pinfunction "DSI_CKP_B16") (pintype "passive+no_connect"))
    )
    (net (code "218") (name "unconnected-(U1C-DSI_D0N-PadB15)") (class "Default")
      (node (ref "U1") (pin "B15") (pinfunction "DSI_D0N_B15") (pintype "passive+no_connect"))
    )
    (net (code "219") (name "unconnected-(U1C-DSI_D0P-PadC15)") (class "Default")
      (node (ref "U1") (pin "C15") (pinfunction "DSI_D0P_C15") (pintype "passive+no_connect"))
    )
    (net (code "220") (name "unconnected-(U1C-DSI_D1N-PadA17)") (class "Default")
      (node (ref "U1") (pin "A17") (pinfunction "DSI_D1N_A17") (pintype "passive+no_connect"))
    )
    (net (code "221") (name "unconnected-(U1C-DSI_D1P-PadB17)") (class "Default")
      (node (ref "U1") (pin "B17") (pinfunction "DSI_D1P_B17") (pintype "passive+no_connect"))
    )
    (net (code "222") (name "unconnected-(U1C-NRST_CORE-PadM4)") (class "Default")
      (node (ref "U1") (pin "M4") (pinfunction "NRST_CORE_M4") (pintype "passive+no_connect"))
    )
    (net (code "223") (name "unconnected-(U1C-PDR_ON-PadR3)") (class "Default")
      (node (ref "U1") (pin "R3") (pinfunction "PDR_ON_R3") (pintype "passive+no_connect"))
    )
    (net (code "224") (name "unconnected-(U1C-PDR_ON_CORE-PadT3)") (class "Default")
      (node (ref "U1") (pin "T3") (pinfunction "PDR_ON_CORE_T3") (pintype "passive+no_connect"))
    )
    (net (code "225") (name "unconnected-(U1C-PI0-PadC1)") (class "Default")
      (node (ref "U1") (pin "C1") (pinfunction "PI0_C1") (pintype "passive+no_connect"))
    )
    (net (code "226") (name "unconnected-(U1C-PI1-PadE3)") (class "Default")
      (node (ref "U1") (pin "E3") (pinfunction "PI1_E3") (pintype "passive+no_connect"))
    )
    (net (code "227") (name "unconnected-(U1C-PI2-PadE2)") (class "Default")
      (node (ref "U1") (pin "E2") (pinfunction "PI2_E2") (pintype "passive+no_connect"))
    )
    (net (code "228") (name "unconnected-(U1C-PI3-PadE1)") (class "Default")
      (node (ref "U1") (pin "E1") (pinfunction "PI3_E1") (pintype "passive+no_connect"))
    )
    (net (code "229") (name "unconnected-(U1C-PI4-PadE4)") (class "Default")
      (node (ref "U1") (pin "E4") (pinfunction "PI4_E4") (pintype "passive+no_connect"))
    )
    (net (code "230") (name "unconnected-(U1C-PI5-PadF3)") (class "Default")
      (node (ref "U1") (pin "F3") (pinfunction "PI5_F3") (pintype "passive+no_connect"))
    )
    (net (code "231") (name "unconnected-(U1C-PI6-PadF4)") (class "Default")
      (node (ref "U1") (pin "F4") (pinfunction "PI6_F4") (pintype "passive+no_connect"))
    )
    (net (code "232") (name "unconnected-(U1C-PI7-PadF2)") (class "Default")
      (node (ref "U1") (pin "F2") (pinfunction "PI7_F2") (pintype "passive+no_connect"))
    )
    (net (code "233") (name "unconnected-(U1C-PI8-PadL4)") (class "Default")
      (node (ref "U1") (pin "L4") (pinfunction "PI8_L4") (pintype "passive+no_connect"))
    )
    (net (code "234") (name "unconnected-(U1C-PI9-PadH4)") (class "Default")
      (node (ref "U1") (pin "H4") (pinfunction "PI9_H4") (pintype "passive+no_connect"))
    )
    (net (code "235") (name "unconnected-(U1C-PI10-PadT1)") (class "Default")
      (node (ref "U1") (pin "T1") (pinfunction "PI10_T1") (pintype "passive+no_connect"))
    )
    (net (code "236") (name "unconnected-(U1C-PI11-PadP4)") (class "Default")
      (node (ref "U1") (pin "P4") (pinfunction "PI11_P4") (pintype "passive+no_connect"))
    )
    (net (code "237") (name "unconnected-(U1C-PWR_LP-PadN3)") (class "Default")
      (node (ref "U1") (pin "N3") (pinfunction "PWR_LP_N3") (pintype "passive+no_connect"))
    )
    (net (code "238") (name "unconnected-(U1C-PZ0-PadG3)") (class "Default")
      (node (ref "U1") (pin "G3") (pinfunction "PZ0_G3") (pintype "passive+no_connect"))
    )
    (net (code "239") (name "unconnected-(U1C-PZ1-PadG1)") (class "Default")
      (node (ref "U1") (pin "G1") (pinfunction "PZ1_G1") (pintype "passive+no_connect"))
    )
    (net (code "240") (name "unconnected-(U1C-PZ2-PadJ4)") (class "Default")
      (node (ref "U1") (pin "J4") (pinfunction "PZ2_J4") (pintype "passive+no_connect"))
    )
    (net (code "241") (name "unconnected-(U1C-PZ3-PadG4)") (class "Default")
      (node (ref "U1") (pin "G4") (pinfunction "PZ3_G4") (pintype "passive+no_connect"))
    )
    (net (code "242") (name "unconnected-(U1C-PZ4-PadG2)") (class "Default")
      (node (ref "U1") (pin "G2") (pinfunction "PZ4_G2") (pintype "passive+no_connect"))
    )
    (net (code "243") (name "unconnected-(U1C-PZ5-PadH2)") (class "Default")
      (node (ref "U1") (pin "H2") (pinfunction "PZ5_H2") (pintype "passive+no_connect"))
    )
    (net (code "244") (name "unconnected-(U1C-PZ6-PadH1)") (class "Default")
      (node (ref "U1") (pin "H1") (pinfunction "PZ6_H1") (pintype "passive+no_connect"))
    )
    (net (code "245") (name "unconnected-(U1C-PZ7-PadJ3)") (class "Default")
      (node (ref "U1") (pin "J3") (pinfunction "PZ7_J3") (pintype "passive+no_connect"))
    )
    (net (code "246") (name "unconnected-(U1E-DDR_A10-PadR22)") (class "Default")
      (node (ref "U1") (pin "R22") (pinfunction "DDR_A10_R22") (pintype "passive+no_connect"))
    )
    (net (code "247") (name "unconnected-(U1E-DDR_A11-PadR20)") (class "Default")
      (node (ref "U1") (pin "R20") (pinfunction "DDR_A11_R20") (pintype "passive+no_connect"))
    )
    (net (code "248") (name "unconnected-(U1E-DDR_A12-PadP23)") (class "Default")
      (node (ref "U1") (pin "P23") (pinfunction "DDR_A12_P23") (pintype "passive+no_connect"))
    )
    (net (code "249") (name "unconnected-(U1E-DDR_A13-PadF20)") (class "Default")
      (node (ref "U1") (pin "F20") (pinfunction "DDR_A13_F20") (pintype "passive+no_connect"))
    )
    (net (code "250") (name "unconnected-(U1E-DDR_A14-PadR21)") (class "Default")
      (node (ref "U1") (pin "R21") (pinfunction "DDR_A14_R21") (pintype "passive+no_connect"))
    )
    (net (code "251") (name "unconnected-(U1E-DDR_A15-PadP20)") (class "Default")
      (node (ref "U1") (pin "P20") (pinfunction "DDR_A15_P20") (pintype "passive+no_connect"))
    )
    (net (code "252") (name "unconnected-(U1E-DDR_ATO-PadY19)") (class "Default")
      (node (ref "U1") (pin "Y19") (pinfunction "DDR_ATO_Y19") (pintype "passive+no_connect"))
    )
    (net (code "253") (name "unconnected-(U1E-DDR_BA0-PadL23)") (class "Default")
      (node (ref "U1") (pin "L23") (pinfunction "DDR_BA0_L23") (pintype "passive+no_connect"))
    )
    (net (code "254") (name "unconnected-(U1E-DDR_BA1-PadU20)") (class "Default")
      (node (ref "U1") (pin "U20") (pinfunction "DDR_BA1_U20") (pintype "passive+no_connect"))
    )
    (net (code "255") (name "unconnected-(U1E-DDR_BA2-PadM21)") (class "Default")
      (node (ref "U1") (pin "M21") (pinfunction "DDR_BA2_M21") (pintype "passive+no_connect"))
    )
    (net (code "256") (name "unconnected-(U1E-DDR_CASN-PadN20)") (class "Default")
      (node (ref "U1") (pin "N20") (pinfunction "DDR_CASN_N20") (pintype "passive+no_connect"))
    )
    (net (code "257") (name "unconnected-(U1E-DDR_DTO0-PadK20)") (class "Default")
      (node (ref "U1") (pin "K20") (pinfunction "DDR_DTO0_K20") (pintype "passive+no_connect"))
    )
    (net (code "258") (name "unconnected-(U1E-DDR_DTO1-PadL21)") (class "Default")
      (node (ref "U1") (pin "L21") (pinfunction "DDR_DTO1_L21") (pintype "passive+no_connect"))
    )
    (net (code "259") (name "unconnected-(U1E-DDR_ODT-PadL22)") (class "Default")
      (node (ref "U1") (pin "L22") (pinfunction "DDR_ODT_L22") (pintype "passive+no_connect"))
    )
    (net (code "260") (name "unconnected-(U1E-DDR_RASN-PadN21)") (class "Default")
      (node (ref "U1") (pin "N21") (pinfunction "DDR_RASN_N21") (pintype "passive+no_connect"))
    )
    (net (code "261") (name "unconnected-(U1E-DDR_RESETN-PadD20)") (class "Default")
      (node (ref "U1") (pin "D20") (pinfunction "DDR_RESETN_D20") (pintype "passive+no_connect"))
    )
    (net (code "262") (name "unconnected-(U1E-DDR_WEN-PadM20)") (class "Default")
      (node (ref "U1") (pin "M20") (pinfunction "DDR_WEN_M20") (pintype "passive+no_connect"))
    )
  )
)
